# Nakaya_Mainboard2.net
KiCad netlist of a schematic drawn in EAGLE
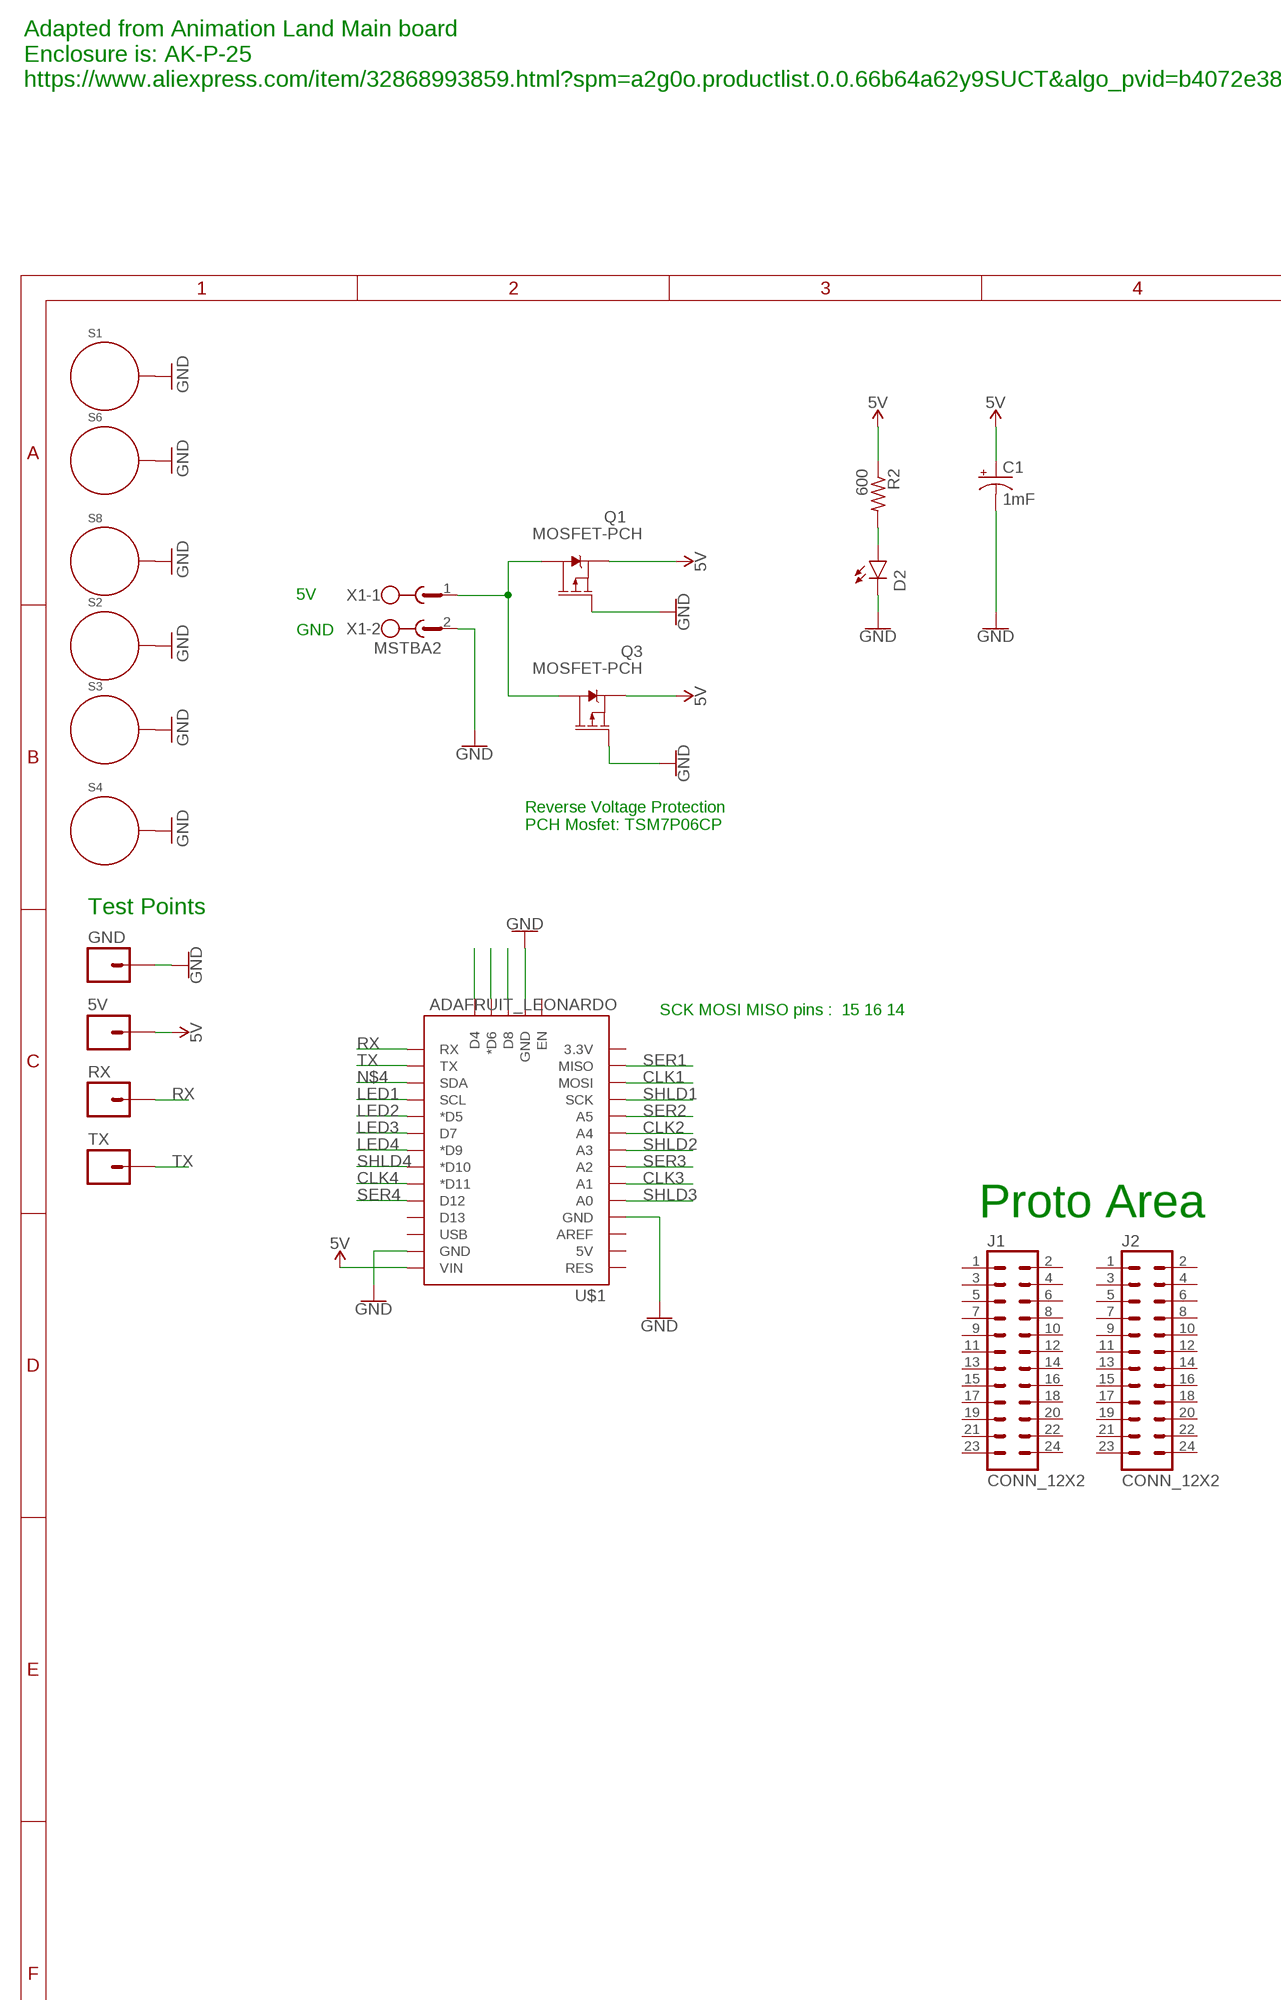
[diagram p0: schematic, sheet 1, part 1 of 2]
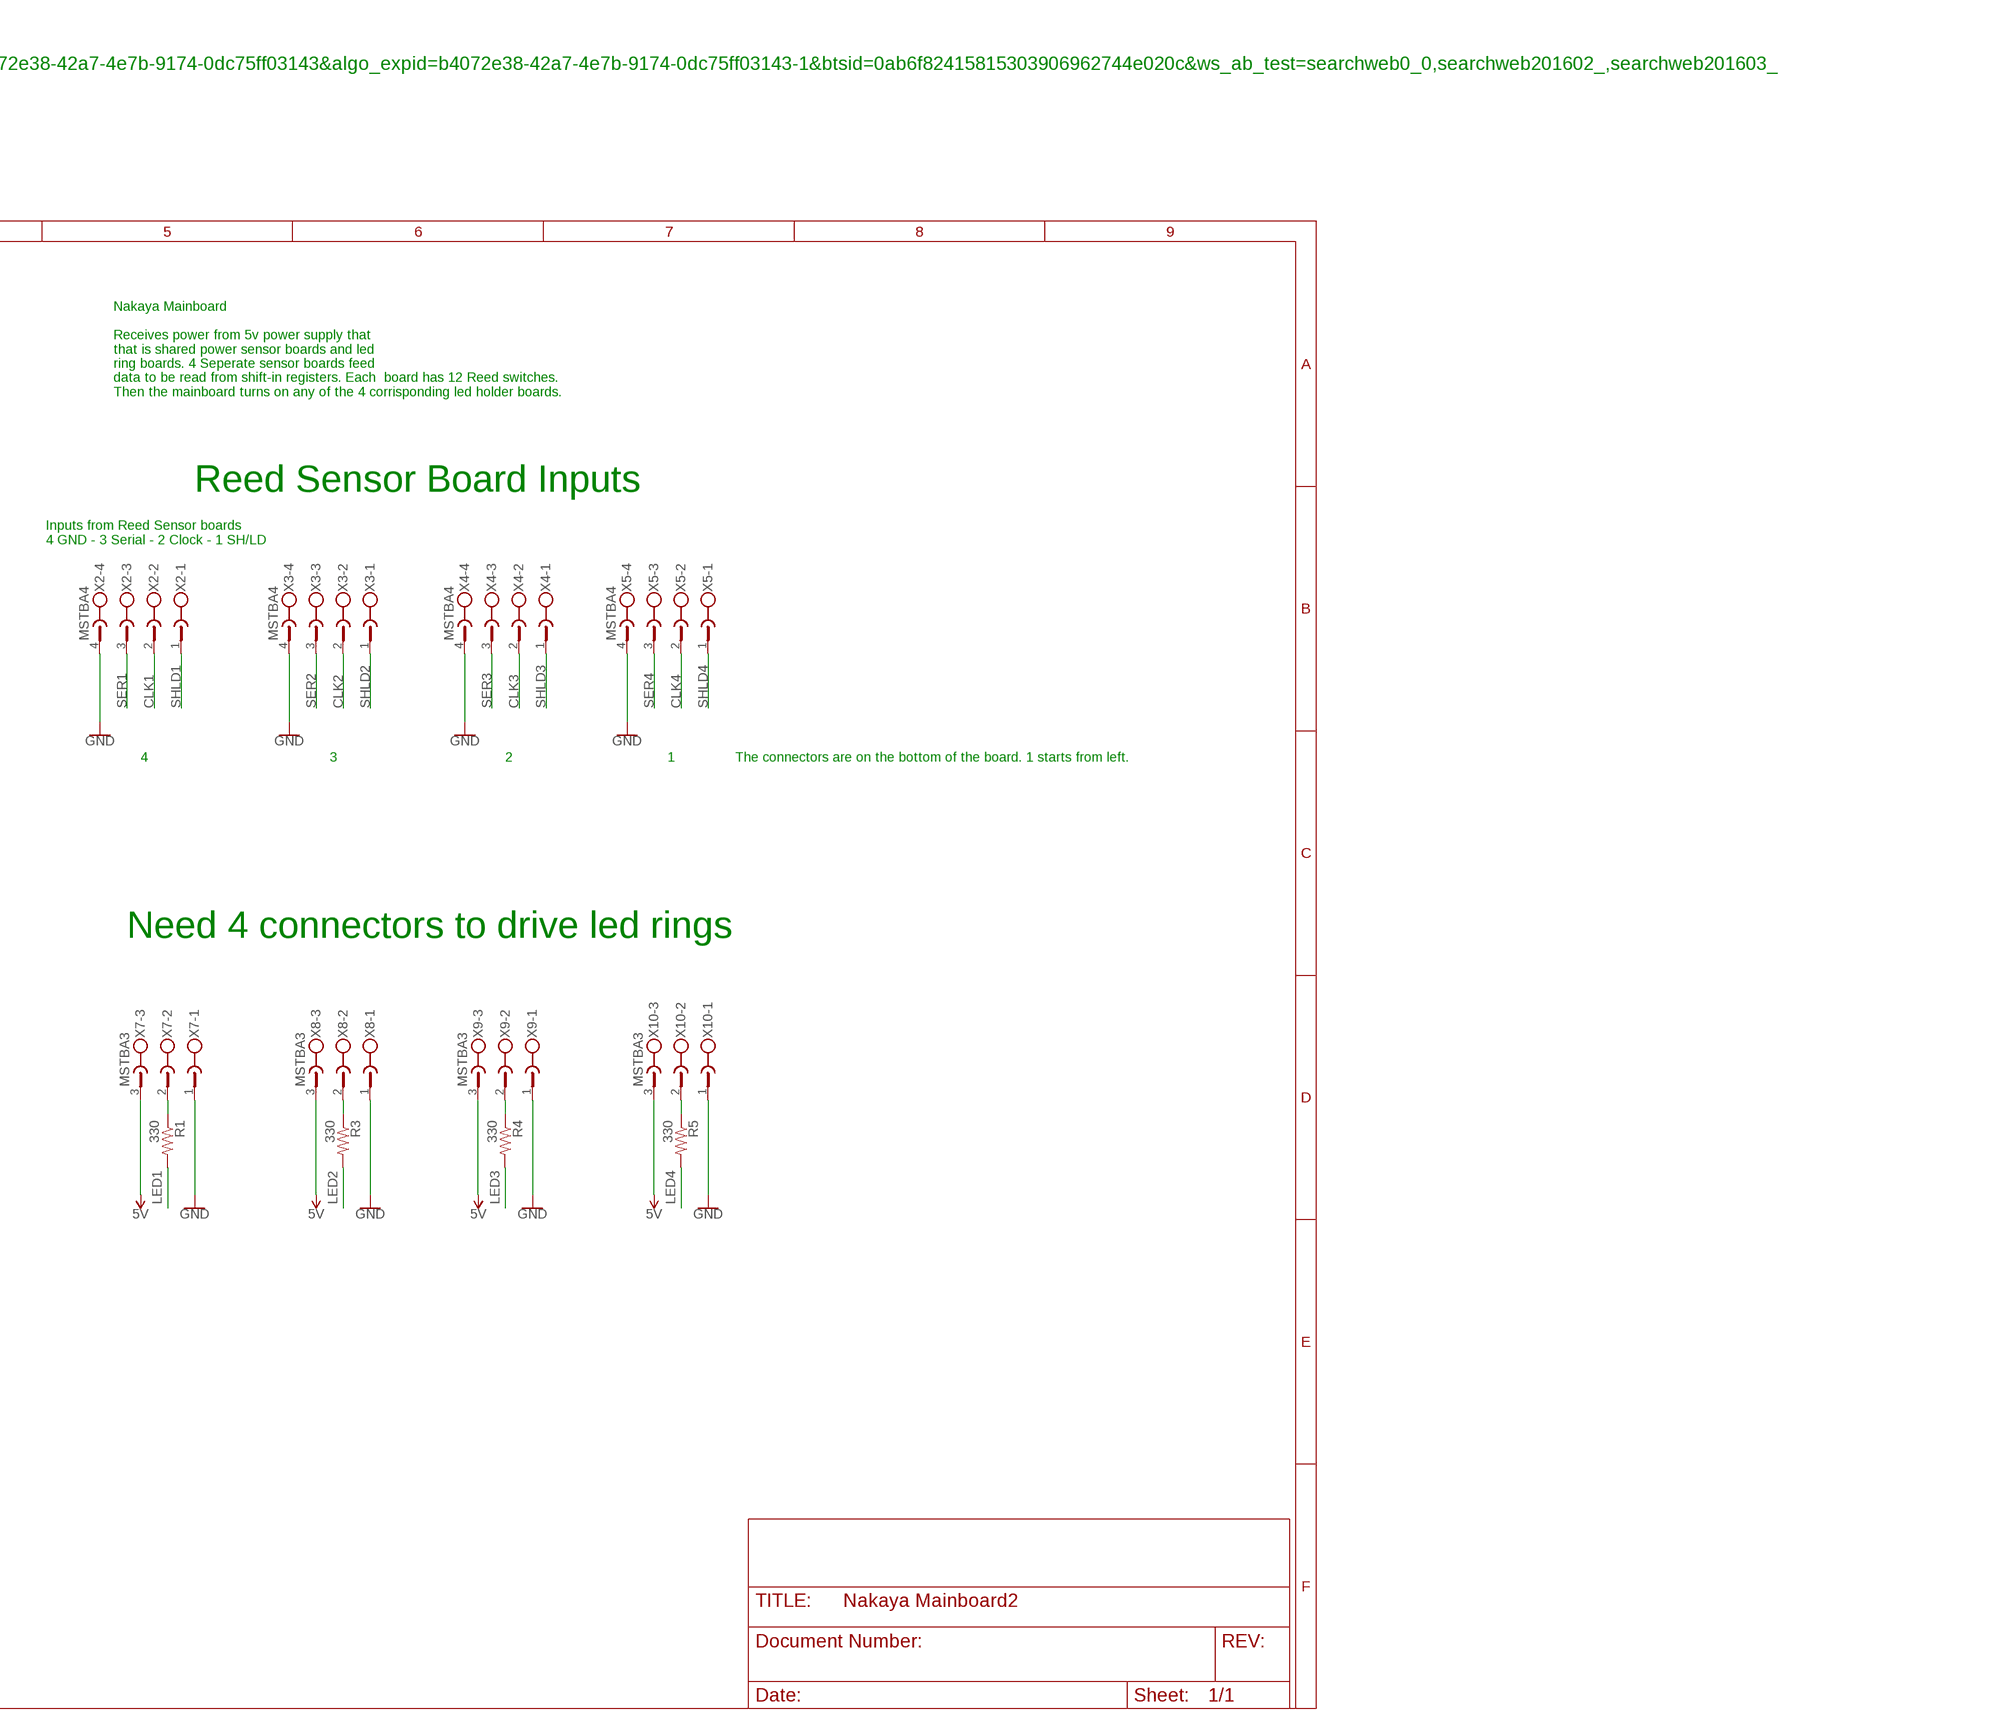
[diagram p1: schematic, sheet 1, part 2 of 2]

(export (version "E")
  (design (tool "Eeschema 10.0.6"))
  (components
    (comp (ref "5V")
      (value "M01PTH")
      (footprint "eagle-import:1X01")
      (libsource (lib "eagle-import") (part "M01PTH"))
    )
    (comp (ref "C1")
      (value "1mF")
      (footprint "eagle-import:CPOL-RADIAL-5MM-10MM")
      (libsource (lib "eagle-import") (part "1000UF-RADIAL-5MM-25V-20%"))
    )
    (comp (ref "D2")
      (value "RED")
      (footprint "eagle-import:SPARKFUN-LED_LED-1206")
      (libsource (lib "eagle-import") (part "SPARKFUN-LED_LED1206"))
    )
    (comp (ref "GND")
      (value "M01PTH")
      (footprint "eagle-import:1X01")
      (libsource (lib "eagle-import") (part "M01PTH"))
    )
    (comp (ref "J1")
      (value "CONN_12X2")
      (footprint "eagle-import:2X12")
      (libsource (lib "eagle-import") (part "CONN_12X2"))
    )
    (comp (ref "J2")
      (value "CONN_12X2")
      (footprint "eagle-import:2X12")
      (libsource (lib "eagle-import") (part "CONN_12X2"))
    )
    (comp (ref "Q1")
      (value "MOSFET-PCH")
      (footprint "eagle-import:DPAK")
      (libsource (lib "eagle-import") (part "MOSFET-PCH"))
    )
    (comp (ref "Q3")
      (value "MOSFET-PCH")
      (footprint "eagle-import:DPAK")
      (libsource (lib "eagle-import") (part "MOSFET-PCH"))
    )
    (comp (ref "R1")
      (value "330")
      (footprint "eagle-import:R0805")
      (libsource (lib "eagle-import") (part "R-US_R0805"))
    )
    (comp (ref "R2")
      (value "600")
      (footprint "eagle-import:R0805")
      (libsource (lib "eagle-import") (part "R-US_R0805"))
    )
    (comp (ref "R3")
      (value "330")
      (footprint "eagle-import:R0805")
      (libsource (lib "eagle-import") (part "R-US_R0805"))
    )
    (comp (ref "R4")
      (value "330")
      (footprint "eagle-import:R0805")
      (libsource (lib "eagle-import") (part "R-US_R0805"))
    )
    (comp (ref "R5")
      (value "330")
      (footprint "eagle-import:R0805")
      (libsource (lib "eagle-import") (part "R-US_R0805"))
    )
    (comp (ref "RX")
      (value "M01PTH")
      (footprint "eagle-import:1X01")
      (libsource (lib "eagle-import") (part "M01PTH"))
    )
    (comp (ref "S1")
      (value "STANDOFF_ELECTRICAL5-32")
      (footprint "eagle-import:STANDOFF_ELECTRICAL_5_32")
      (libsource (lib "eagle-import") (part "STANDOFF_ELECTRICAL5-32"))
    )
    (comp (ref "S2")
      (value "STANDOFF_ELECTRICAL5-32")
      (footprint "eagle-import:STANDOFF_ELECTRICAL_5_32")
      (libsource (lib "eagle-import") (part "STANDOFF_ELECTRICAL5-32"))
    )
    (comp (ref "S3")
      (value "STANDOFF_ELECTRICAL5-32")
      (footprint "eagle-import:STANDOFF_ELECTRICAL_5_32")
      (libsource (lib "eagle-import") (part "STANDOFF_ELECTRICAL5-32"))
    )
    (comp (ref "S4")
      (value "STANDOFF_ELECTRICAL5-32")
      (footprint "eagle-import:STANDOFF_ELECTRICAL_5_32")
      (libsource (lib "eagle-import") (part "STANDOFF_ELECTRICAL5-32"))
    )
    (comp (ref "S6")
      (value "STANDOFF_ELECTRICAL5-32")
      (footprint "eagle-import:STANDOFF_ELECTRICAL_5_32")
      (libsource (lib "eagle-import") (part "STANDOFF_ELECTRICAL5-32"))
    )
    (comp (ref "S8")
      (value "STANDOFF_ELECTRICAL5-32")
      (footprint "eagle-import:STANDOFF_ELECTRICAL_5_32")
      (libsource (lib "eagle-import") (part "STANDOFF_ELECTRICAL5-32"))
    )
    (comp (ref "TX")
      (value "M01PTH")
      (footprint "eagle-import:1X01")
      (libsource (lib "eagle-import") (part "M01PTH"))
    )
    (comp (ref "U$1")
      (value "ADAFRUIT_LEONARDO")
      (footprint "eagle-import:ADAFRUIT_LENOARDO")
      (libsource (lib "eagle-import") (part "ADAFRUIT_LEONARDO"))
    )
    (comp (ref "X1")
      (value "MSTBA2")
      (footprint "eagle-import:MSTBA2")
      (fields (field (name "MF") "FARNELL") (field (name "MPN") "1757242"))
      (libsource (lib "eagle-import") (part "MSTBA2"))
    )
    (comp (ref "X2")
      (value "MSTBA4")
      (footprint "eagle-import:MSTBA4")
      (fields (field (name "MF") "FARNELL") (field (name "MPN") "1757268"))
      (libsource (lib "eagle-import") (part "MSTBA4"))
    )
    (comp (ref "X3")
      (value "MSTBA4")
      (footprint "eagle-import:MSTBA4")
      (fields (field (name "MF") "FARNELL") (field (name "MPN") "1757268"))
      (libsource (lib "eagle-import") (part "MSTBA4"))
    )
    (comp (ref "X4")
      (value "MSTBA4")
      (footprint "eagle-import:MSTBA4")
      (fields (field (name "MF") "FARNELL") (field (name "MPN") "1757268"))
      (libsource (lib "eagle-import") (part "MSTBA4"))
    )
    (comp (ref "X5")
      (value "MSTBA4")
      (footprint "eagle-import:MSTBA4")
      (fields (field (name "MF") "FARNELL") (field (name "MPN") "1757268"))
      (libsource (lib "eagle-import") (part "MSTBA4"))
    )
    (comp (ref "X7")
      (value "MSTBA3")
      (footprint "eagle-import:MSTBA3")
      (fields (field (name "MF") "FARNELL") (field (name "MPN") "1757255"))
      (libsource (lib "eagle-import") (part "MSTBA3"))
    )
    (comp (ref "X8")
      (value "MSTBA3")
      (footprint "eagle-import:MSTBA3")
      (fields (field (name "MF") "FARNELL") (field (name "MPN") "1757255"))
      (libsource (lib "eagle-import") (part "MSTBA3"))
    )
    (comp (ref "X9")
      (value "MSTBA3")
      (footprint "eagle-import:MSTBA3")
      (fields (field (name "MF") "FARNELL") (field (name "MPN") "1757255"))
      (libsource (lib "eagle-import") (part "MSTBA3"))
    )
    (comp (ref "X10")
      (value "MSTBA3")
      (footprint "eagle-import:MSTBA3")
      (fields (field (name "MF") "FARNELL") (field (name "MPN") "1757255"))
      (libsource (lib "eagle-import") (part "MSTBA3"))
    )
  )
  (nets
    (net (code "1") (name "/CLK1") (class "Default")
      (node (ref "U$1") (pin "MOSI") (pinfunction "MOSI_MOSI") (pintype "bidirectional"))
      (node (ref "X2") (pin "2") (pinfunction "1_2") (pintype "passive"))
    )
    (net (code "2") (name "/CLK2") (class "Default")
      (node (ref "U$1") (pin "A4") (pinfunction "A4_A4") (pintype "bidirectional"))
      (node (ref "X3") (pin "2") (pinfunction "1_2") (pintype "passive"))
    )
    (net (code "3") (name "/CLK3") (class "Default")
      (node (ref "U$1") (pin "A1") (pinfunction "A1_A1") (pintype "bidirectional"))
      (node (ref "X4") (pin "2") (pinfunction "1_2") (pintype "passive"))
    )
    (net (code "4") (name "/CLK4") (class "Default")
      (node (ref "U$1") (pin "D11") (pinfunction "*D11_D11") (pintype "bidirectional"))
      (node (ref "X5") (pin "2") (pinfunction "1_2") (pintype "passive"))
    )
    (net (code "5") (name "/LED1") (class "Default")
      (node (ref "R1") (pin "2") (pinfunction "2_2") (pintype "passive"))
      (node (ref "U$1") (pin "SCL") (pinfunction "SCL_SCL") (pintype "bidirectional"))
    )
    (net (code "6") (name "/LED2") (class "Default")
      (node (ref "R3") (pin "2") (pinfunction "2_2") (pintype "passive"))
      (node (ref "U$1") (pin "D5") (pinfunction "*D5_D5") (pintype "bidirectional"))
    )
    (net (code "7") (name "/LED3") (class "Default")
      (node (ref "R4") (pin "2") (pinfunction "2_2") (pintype "passive"))
      (node (ref "U$1") (pin "D7") (pinfunction "D7_D7") (pintype "bidirectional"))
    )
    (net (code "8") (name "/LED4") (class "Default")
      (node (ref "R5") (pin "2") (pinfunction "2_2") (pintype "passive"))
      (node (ref "U$1") (pin "D9") (pinfunction "*D9_D9") (pintype "bidirectional"))
    )
    (net (code "9") (name "/N$4") (class "Default")
      (node (ref "U$1") (pin "SDA") (pinfunction "SDA_SDA") (pintype "bidirectional"))
    )
    (net (code "10") (name "/RX") (class "Default")
      (node (ref "RX") (pin "1") (pinfunction "1_1") (pintype "passive"))
      (node (ref "U$1") (pin "RX") (pinfunction "RX_RX") (pintype "bidirectional"))
    )
    (net (code "11") (name "/SER1") (class "Default")
      (node (ref "U$1") (pin "MISO") (pinfunction "MISO_MISO") (pintype "bidirectional"))
      (node (ref "X2") (pin "3") (pinfunction "1_3") (pintype "passive"))
    )
    (net (code "12") (name "/SER2") (class "Default")
      (node (ref "U$1") (pin "A5") (pinfunction "A5_A5") (pintype "bidirectional"))
      (node (ref "X3") (pin "3") (pinfunction "1_3") (pintype "passive"))
    )
    (net (code "13") (name "/SER3") (class "Default")
      (node (ref "U$1") (pin "A2") (pinfunction "A2_A2") (pintype "bidirectional"))
      (node (ref "X4") (pin "3") (pinfunction "1_3") (pintype "passive"))
    )
    (net (code "14") (name "/SER4") (class "Default")
      (node (ref "U$1") (pin "D12") (pinfunction "D12_D12") (pintype "bidirectional"))
      (node (ref "X5") (pin "3") (pinfunction "1_3") (pintype "passive"))
    )
    (net (code "15") (name "/SHLD1") (class "Default")
      (node (ref "U$1") (pin "SCK") (pinfunction "SCK_SCK") (pintype "bidirectional"))
      (node (ref "X2") (pin "1") (pinfunction "1_1") (pintype "passive"))
    )
    (net (code "16") (name "/SHLD2") (class "Default")
      (node (ref "U$1") (pin "A3") (pinfunction "A3_A3") (pintype "bidirectional"))
      (node (ref "X3") (pin "1") (pinfunction "1_1") (pintype "passive"))
    )
    (net (code "17") (name "/SHLD3") (class "Default")
      (node (ref "U$1") (pin "A0") (pinfunction "A0_A0") (pintype "bidirectional"))
      (node (ref "X4") (pin "1") (pinfunction "1_1") (pintype "passive"))
    )
    (net (code "18") (name "/SHLD4") (class "Default")
      (node (ref "U$1") (pin "D10") (pinfunction "*D10_D10") (pintype "bidirectional"))
      (node (ref "X5") (pin "1") (pinfunction "1_1") (pintype "passive"))
    )
    (net (code "19") (name "/TX") (class "Default")
      (node (ref "TX") (pin "1") (pinfunction "1_1") (pintype "passive"))
      (node (ref "U$1") (pin "TX") (pinfunction "TX_TX") (pintype "bidirectional"))
    )
    (net (code "20") (name "5V") (class "Default")
      (node (ref "5V") (pin "1") (pinfunction "1_1") (pintype "passive"))
      (node (ref "C1") (pin "+") (pinfunction "+_+") (pintype "passive"))
      (node (ref "Q1") (pin "3") (pinfunction "S_3") (pintype "bidirectional"))
      (node (ref "Q3") (pin "3") (pinfunction "S_3") (pintype "bidirectional"))
      (node (ref "R2") (pin "1") (pinfunction "1_1") (pintype "passive"))
      (node (ref "U$1") (pin "VIN") (pinfunction "VIN_VIN") (pintype "bidirectional"))
      (node (ref "X10") (pin "3") (pinfunction "1_3") (pintype "passive"))
      (node (ref "X7") (pin "3") (pinfunction "1_3") (pintype "passive"))
      (node (ref "X8") (pin "3") (pinfunction "1_3") (pintype "passive"))
      (node (ref "X9") (pin "3") (pinfunction "1_3") (pintype "passive"))
    )
    (net (code "21") (name "GND") (class "Default")
      (node (ref "C1") (pin "-") (pinfunction "-_-") (pintype "passive"))
      (node (ref "D2") (pin "C") (pinfunction "C_C") (pintype "passive"))
      (node (ref "GND") (pin "1") (pinfunction "1_1") (pintype "passive"))
      (node (ref "Q1") (pin "1") (pinfunction "G_1") (pintype "bidirectional"))
      (node (ref "Q3") (pin "1") (pinfunction "G_1") (pintype "bidirectional"))
      (node (ref "S1") (pin "P1") (pinfunction "P$1_P1") (pintype "bidirectional"))
      (node (ref "S2") (pin "P1") (pinfunction "P$1_P1") (pintype "bidirectional"))
      (node (ref "S3") (pin "P1") (pinfunction "P$1_P1") (pintype "bidirectional"))
      (node (ref "S4") (pin "P1") (pinfunction "P$1_P1") (pintype "bidirectional"))
      (node (ref "S6") (pin "P1") (pinfunction "P$1_P1") (pintype "bidirectional"))
      (node (ref "S8") (pin "P1") (pinfunction "P$1_P1") (pintype "bidirectional"))
      (node (ref "U$1") (pin "GND@0") (pinfunction "GND_GND@0") (pintype "bidirectional"))
      (node (ref "U$1") (pin "GND@1") (pinfunction "GND_GND@1") (pintype "bidirectional"))
      (node (ref "U$1") (pin "GND@2") (pinfunction "GND_GND@2") (pintype "bidirectional"))
      (node (ref "X1") (pin "2") (pinfunction "1_2") (pintype "passive"))
      (node (ref "X10") (pin "1") (pinfunction "1_1") (pintype "passive"))
      (node (ref "X2") (pin "4") (pinfunction "1_4") (pintype "passive"))
      (node (ref "X3") (pin "4") (pinfunction "1_4") (pintype "passive"))
      (node (ref "X4") (pin "4") (pinfunction "1_4") (pintype "passive"))
      (node (ref "X5") (pin "4") (pinfunction "1_4") (pintype "passive"))
      (node (ref "X7") (pin "1") (pinfunction "1_1") (pintype "passive"))
      (node (ref "X8") (pin "1") (pinfunction "1_1") (pintype "passive"))
      (node (ref "X9") (pin "1") (pinfunction "1_1") (pintype "passive"))
    )
    (net (code "22") (name "Net-(D2-PadA)") (class "Default")
      (node (ref "D2") (pin "A") (pinfunction "A_A") (pintype "passive"))
      (node (ref "R2") (pin "2") (pinfunction "2_2") (pintype "passive"))
    )
    (net (code "23") (name "Net-(Q1-D)") (class "Default")
      (node (ref "Q1") (pin "4") (pinfunction "D_4") (pintype "bidirectional"))
      (node (ref "Q3") (pin "4") (pinfunction "D_4") (pintype "bidirectional"))
      (node (ref "X1") (pin "1") (pinfunction "1_1") (pintype "passive"))
    )
    (net (code "24") (name "Net-(X7B-1)") (class "Default")
      (node (ref "R1") (pin "1") (pinfunction "1_1") (pintype "passive"))
      (node (ref "X7") (pin "2") (pinfunction "1_2") (pintype "passive"))
    )
    (net (code "25") (name "Net-(X8B-1)") (class "Default")
      (node (ref "R3") (pin "1") (pinfunction "1_1") (pintype "passive"))
      (node (ref "X8") (pin "2") (pinfunction "1_2") (pintype "passive"))
    )
    (net (code "26") (name "Net-(X9B-1)") (class "Default")
      (node (ref "R4") (pin "1") (pinfunction "1_1") (pintype "passive"))
      (node (ref "X9") (pin "2") (pinfunction "1_2") (pintype "passive"))
    )
    (net (code "27") (name "Net-(X10B-1)") (class "Default")
      (node (ref "R5") (pin "1") (pinfunction "1_1") (pintype "passive"))
      (node (ref "X10") (pin "2") (pinfunction "1_2") (pintype "passive"))
    )
    (net (code "28") (name "unconnected-(J1-Pad1)") (class "Default")
      (node (ref "J1") (pin "1") (pinfunction "1_1") (pintype "passive"))
    )
    (net (code "29") (name "unconnected-(J1-Pad2)") (class "Default")
      (node (ref "J1") (pin "2") (pinfunction "2_2") (pintype "passive"))
    )
    (net (code "30") (name "unconnected-(J1-Pad3)") (class "Default")
      (node (ref "J1") (pin "3") (pinfunction "3_3") (pintype "passive"))
    )
    (net (code "31") (name "unconnected-(J1-Pad4)") (class "Default")
      (node (ref "J1") (pin "4") (pinfunction "4_4") (pintype "passive"))
    )
    (net (code "32") (name "unconnected-(J1-Pad5)") (class "Default")
      (node (ref "J1") (pin "5") (pinfunction "5_5") (pintype "passive"))
    )
    (net (code "33") (name "unconnected-(J1-Pad6)") (class "Default")
      (node (ref "J1") (pin "6") (pinfunction "6_6") (pintype "passive"))
    )
    (net (code "34") (name "unconnected-(J1-Pad7)") (class "Default")
      (node (ref "J1") (pin "7") (pinfunction "7_7") (pintype "passive"))
    )
    (net (code "35") (name "unconnected-(J1-Pad8)") (class "Default")
      (node (ref "J1") (pin "8") (pinfunction "8_8") (pintype "passive"))
    )
    (net (code "36") (name "unconnected-(J1-Pad9)") (class "Default")
      (node (ref "J1") (pin "9") (pinfunction "9_9") (pintype "passive"))
    )
    (net (code "37") (name "unconnected-(J1-Pad10)") (class "Default")
      (node (ref "J1") (pin "10") (pinfunction "10_10") (pintype "passive"))
    )
    (net (code "38") (name "unconnected-(J1-Pad11)") (class "Default")
      (node (ref "J1") (pin "11") (pinfunction "11_11") (pintype "passive"))
    )
    (net (code "39") (name "unconnected-(J1-Pad12)") (class "Default")
      (node (ref "J1") (pin "12") (pinfunction "12_12") (pintype "passive"))
    )
    (net (code "40") (name "unconnected-(J1-Pad13)") (class "Default")
      (node (ref "J1") (pin "13") (pinfunction "13_13") (pintype "passive"))
    )
    (net (code "41") (name "unconnected-(J1-Pad14)") (class "Default")
      (node (ref "J1") (pin "14") (pinfunction "14_14") (pintype "passive"))
    )
    (net (code "42") (name "unconnected-(J1-Pad15)") (class "Default")
      (node (ref "J1") (pin "15") (pinfunction "15_15") (pintype "passive"))
    )
    (net (code "43") (name "unconnected-(J1-Pad16)") (class "Default")
      (node (ref "J1") (pin "16") (pinfunction "16_16") (pintype "passive"))
    )
    (net (code "44") (name "unconnected-(J1-Pad17)") (class "Default")
      (node (ref "J1") (pin "17") (pinfunction "17_17") (pintype "passive"))
    )
    (net (code "45") (name "unconnected-(J1-Pad18)") (class "Default")
      (node (ref "J1") (pin "18") (pinfunction "18_18") (pintype "passive"))
    )
    (net (code "46") (name "unconnected-(J1-Pad19)") (class "Default")
      (node (ref "J1") (pin "19") (pinfunction "19_19") (pintype "passive"))
    )
    (net (code "47") (name "unconnected-(J1-Pad20)") (class "Default")
      (node (ref "J1") (pin "20") (pinfunction "20_20") (pintype "passive"))
    )
    (net (code "48") (name "unconnected-(J1-Pad21)") (class "Default")
      (node (ref "J1") (pin "21") (pinfunction "21_21") (pintype "passive"))
    )
    (net (code "49") (name "unconnected-(J1-Pad22)") (class "Default")
      (node (ref "J1") (pin "22") (pinfunction "22_22") (pintype "passive"))
    )
    (net (code "50") (name "unconnected-(J1-Pad23)") (class "Default")
      (node (ref "J1") (pin "23") (pinfunction "23_23") (pintype "passive"))
    )
    (net (code "51") (name "unconnected-(J1-Pad24)") (class "Default")
      (node (ref "J1") (pin "24") (pinfunction "24_24") (pintype "passive"))
    )
    (net (code "52") (name "unconnected-(J2-Pad1)") (class "Default")
      (node (ref "J2") (pin "1") (pinfunction "1_1") (pintype "passive"))
    )
    (net (code "53") (name "unconnected-(J2-Pad2)") (class "Default")
      (node (ref "J2") (pin "2") (pinfunction "2_2") (pintype "passive"))
    )
    (net (code "54") (name "unconnected-(J2-Pad3)") (class "Default")
      (node (ref "J2") (pin "3") (pinfunction "3_3") (pintype "passive"))
    )
    (net (code "55") (name "unconnected-(J2-Pad4)") (class "Default")
      (node (ref "J2") (pin "4") (pinfunction "4_4") (pintype "passive"))
    )
    (net (code "56") (name "unconnected-(J2-Pad5)") (class "Default")
      (node (ref "J2") (pin "5") (pinfunction "5_5") (pintype "passive"))
    )
    (net (code "57") (name "unconnected-(J2-Pad6)") (class "Default")
      (node (ref "J2") (pin "6") (pinfunction "6_6") (pintype "passive"))
    )
    (net (code "58") (name "unconnected-(J2-Pad7)") (class "Default")
      (node (ref "J2") (pin "7") (pinfunction "7_7") (pintype "passive"))
    )
    (net (code "59") (name "unconnected-(J2-Pad8)") (class "Default")
      (node (ref "J2") (pin "8") (pinfunction "8_8") (pintype "passive"))
    )
    (net (code "60") (name "unconnected-(J2-Pad9)") (class "Default")
      (node (ref "J2") (pin "9") (pinfunction "9_9") (pintype "passive"))
    )
    (net (code "61") (name "unconnected-(J2-Pad10)") (class "Default")
      (node (ref "J2") (pin "10") (pinfunction "10_10") (pintype "passive"))
    )
    (net (code "62") (name "unconnected-(J2-Pad11)") (class "Default")
      (node (ref "J2") (pin "11") (pinfunction "11_11") (pintype "passive"))
    )
    (net (code "63") (name "unconnected-(J2-Pad12)") (class "Default")
      (node (ref "J2") (pin "12") (pinfunction "12_12") (pintype "passive"))
    )
    (net (code "64") (name "unconnected-(J2-Pad13)") (class "Default")
      (node (ref "J2") (pin "13") (pinfunction "13_13") (pintype "passive"))
    )
    (net (code "65") (name "unconnected-(J2-Pad14)") (class "Default")
      (node (ref "J2") (pin "14") (pinfunction "14_14") (pintype "passive"))
    )
    (net (code "66") (name "unconnected-(J2-Pad15)") (class "Default")
      (node (ref "J2") (pin "15") (pinfunction "15_15") (pintype "passive"))
    )
    (net (code "67") (name "unconnected-(J2-Pad16)") (class "Default")
      (node (ref "J2") (pin "16") (pinfunction "16_16") (pintype "passive"))
    )
    (net (code "68") (name "unconnected-(J2-Pad17)") (class "Default")
      (node (ref "J2") (pin "17") (pinfunction "17_17") (pintype "passive"))
    )
    (net (code "69") (name "unconnected-(J2-Pad18)") (class "Default")
      (node (ref "J2") (pin "18") (pinfunction "18_18") (pintype "passive"))
    )
    (net (code "70") (name "unconnected-(J2-Pad19)") (class "Default")
      (node (ref "J2") (pin "19") (pinfunction "19_19") (pintype "passive"))
    )
    (net (code "71") (name "unconnected-(J2-Pad20)") (class "Default")
      (node (ref "J2") (pin "20") (pinfunction "20_20") (pintype "passive"))
    )
    (net (code "72") (name "unconnected-(J2-Pad21)") (class "Default")
      (node (ref "J2") (pin "21") (pinfunction "21_21") (pintype "passive"))
    )
    (net (code "73") (name "unconnected-(J2-Pad22)") (class "Default")
      (node (ref "J2") (pin "22") (pinfunction "22_22") (pintype "passive"))
    )
    (net (code "74") (name "unconnected-(J2-Pad23)") (class "Default")
      (node (ref "J2") (pin "23") (pinfunction "23_23") (pintype "passive"))
    )
    (net (code "75") (name "unconnected-(J2-Pad24)") (class "Default")
      (node (ref "J2") (pin "24") (pinfunction "24_24") (pintype "passive"))
    )
    (net (code "76") (name "unconnected-(U$1-*D6-PadD6)") (class "Default")
      (node (ref "U$1") (pin "D6") (pinfunction "*D6_D6") (pintype "bidirectional"))
    )
    (net (code "77") (name "unconnected-(U$1-3.3V-Pad3V)") (class "Default")
      (node (ref "U$1") (pin "3V") (pinfunction "3.3V_3V") (pintype "bidirectional"))
    )
    (net (code "78") (name "unconnected-(U$1-Pad5V)") (class "Default")
      (node (ref "U$1") (pin "5V") (pinfunction "5V_5V") (pintype "bidirectional"))
    )
    (net (code "79") (name "unconnected-(U$1-PadAREF)") (class "Default")
      (node (ref "U$1") (pin "AREF") (pinfunction "AREF_AREF") (pintype "bidirectional"))
    )
    (net (code "80") (name "unconnected-(U$1-PadD4)") (class "Default")
      (node (ref "U$1") (pin "D4") (pinfunction "D4_D4") (pintype "bidirectional"))
    )
    (net (code "81") (name "unconnected-(U$1-PadD8)") (class "Default")
      (node (ref "U$1") (pin "D8") (pinfunction "D8_D8") (pintype "bidirectional"))
    )
    (net (code "82") (name "unconnected-(U$1-PadD13)") (class "Default")
      (node (ref "U$1") (pin "D13") (pinfunction "D13_D13") (pintype "bidirectional"))
    )
    (net (code "83") (name "unconnected-(U$1-PadEN)") (class "Default")
      (node (ref "U$1") (pin "EN") (pinfunction "EN_EN") (pintype "bidirectional"))
    )
    (net (code "84") (name "unconnected-(U$1-PadRES)") (class "Default")
      (node (ref "U$1") (pin "RES") (pinfunction "RES_RES") (pintype "bidirectional"))
    )
    (net (code "85") (name "unconnected-(U$1-PadUSB)") (class "Default")
      (node (ref "U$1") (pin "USB") (pinfunction "USB_USB") (pintype "bidirectional"))
    )
  )
)
